# zigduino-v6c.net
KiCad netlist of a schematic drawn in EAGLE
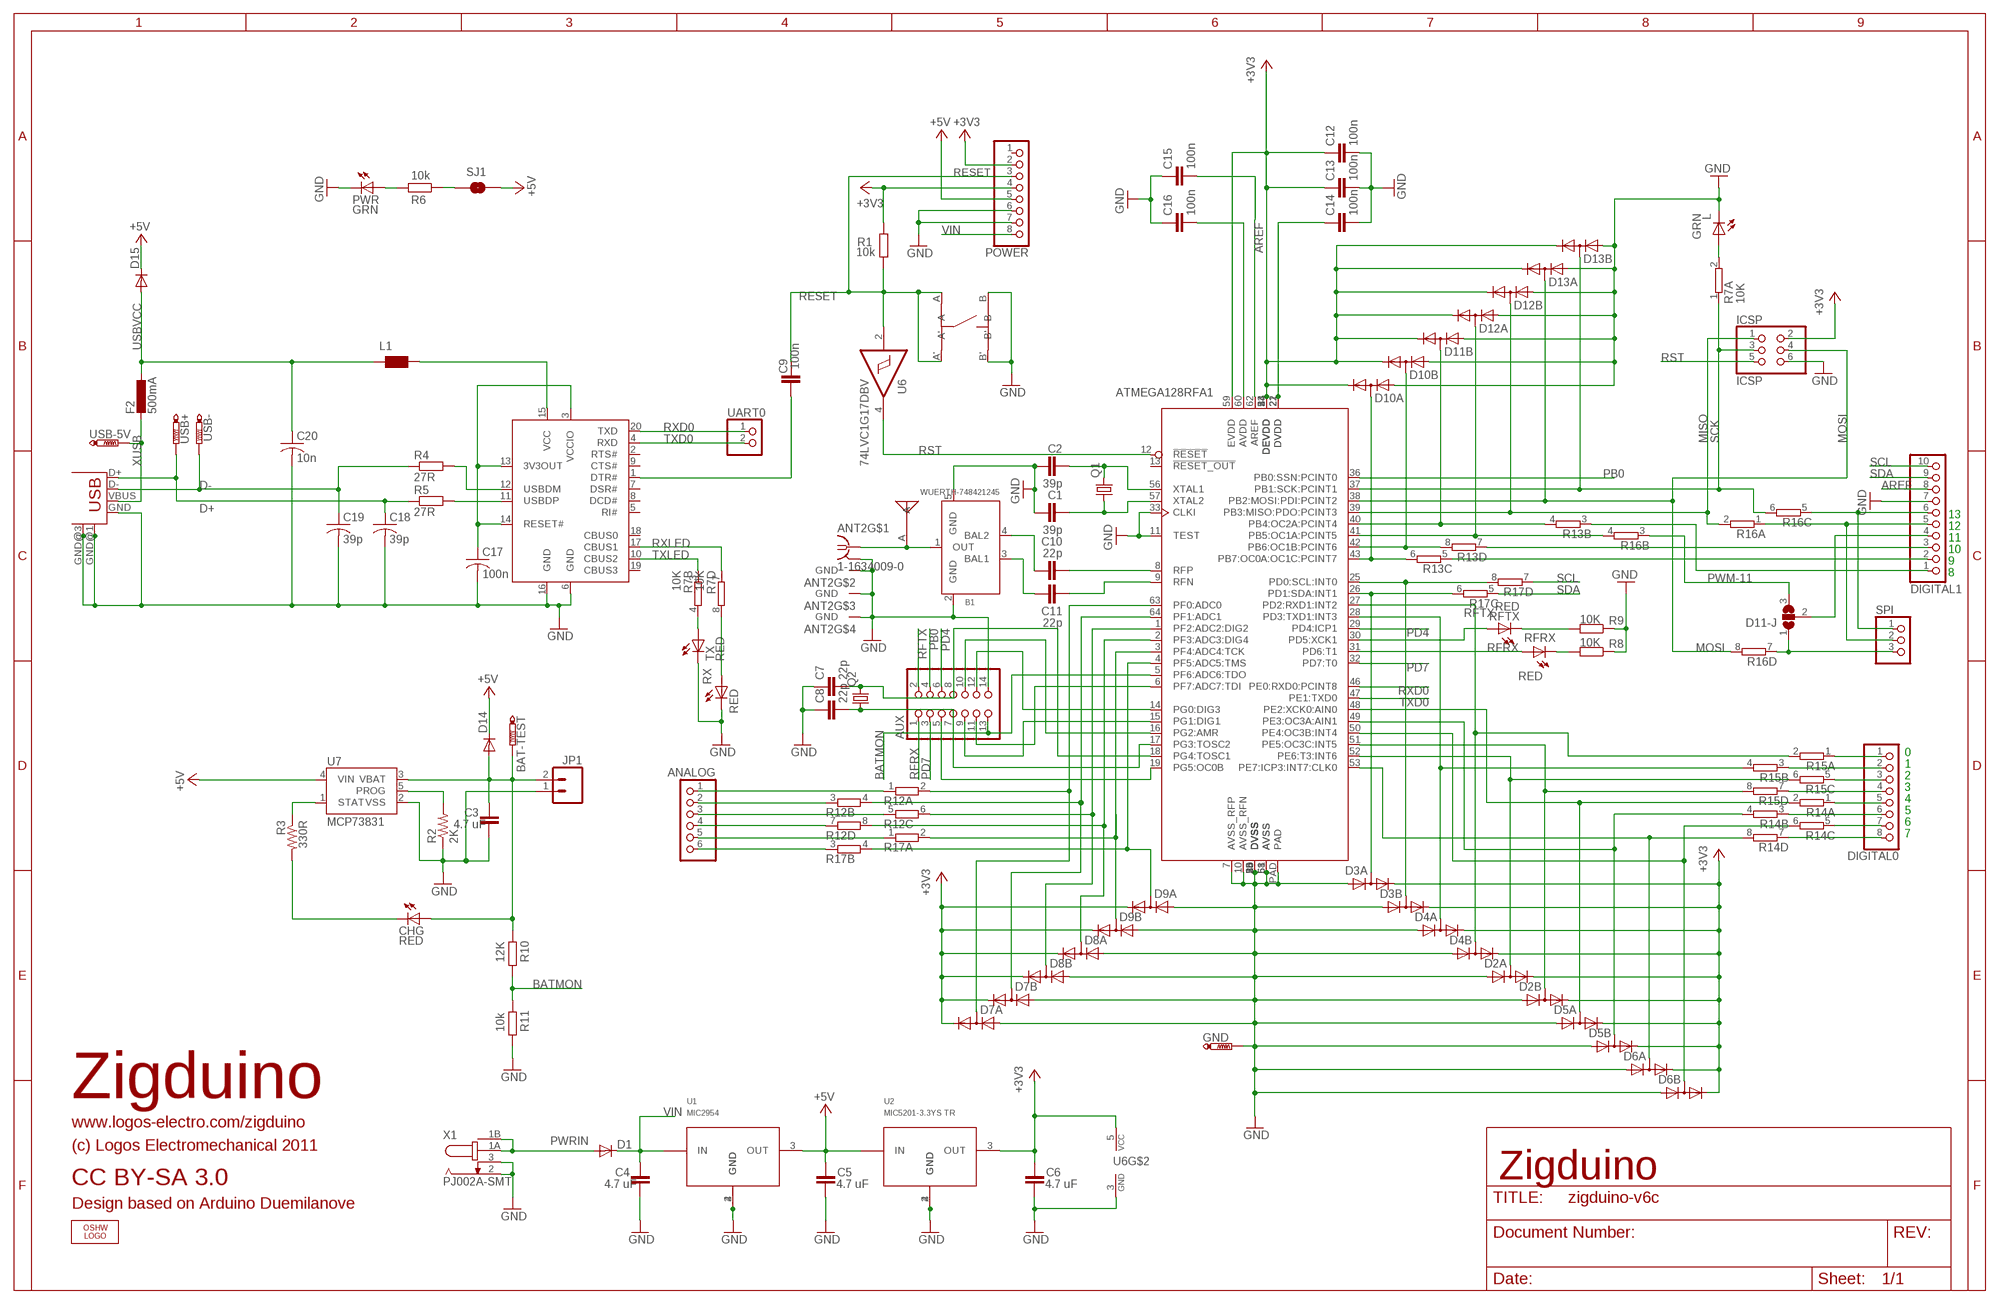
[diagram p0: schematic, sheet 1]

(export (version "E")
  (design (tool "Eeschema 10.0.6"))
  (components
    (comp (ref "ANALOG")
      (value "PINHD-1X6")
      (footprint "eagle-import:1X06")
      (fields (field (name "PARTNO") "19742"))
      (libsource (lib "eagle-import") (part "PINHD-1X6"))
    )
    (comp (ref "ANT1")
      (value "MOLEX-ANT")
      (footprint "eagle-import:MOLEX-ANT")
      (fields (field (name "PARTNO") "0479480001"))
      (libsource (lib "eagle-import") (part "MOLEX-ANT"))
    )
    (comp (ref "ANT2")
      (value "1-1634009-0")
      (footprint "eagle-import:MMCX-THRU")
      (fields (field (name "BOM") "EXCLUDE") (field (name "DNP") "T"))
      (libsource (lib "eagle-import") (part "1-1634009-0"))
    )
    (comp (ref "AUX")
      (value "PINHD-2X7_2.00")
      (footprint "eagle-import:2X07M")
      (fields (field (name "PARTNO") "00217"))
      (libsource (lib "eagle-import") (part "PINHD-2X7_2.00"))
    )
    (comp (ref "B1")
      (value "WUERTH-748421245")
      (footprint "eagle-import:WURTH-BALUN")
      (fields (field (name "PARTNO") "748421245"))
      (libsource (lib "eagle-import") (part "WUERTH-748421245"))
    )
    (comp (ref "BAT-TEST")
      (value "PTR1TP13SQ")
      (footprint "eagle-import:TP13SQ")
      (fields (field (name "PARTNO") "TP13"))
      (libsource (lib "eagle-import") (part "PTR1TP13SQ"))
    )
    (comp (ref "C1")
      (value "39p")
      (footprint "eagle-import:C0603")
      (fields (field (name "PARTNO") "C1608C0G1H390J"))
      (libsource (lib "eagle-import") (part "C-EUC0603"))
    )
    (comp (ref "C2")
      (value "39p")
      (footprint "eagle-import:C0603")
      (fields (field (name "PARTNO") "C1608C0G1H390J"))
      (libsource (lib "eagle-import") (part "C-EUC0603"))
    )
    (comp (ref "C3")
      (value "4.7 uF")
      (footprint "eagle-import:C1206")
      (fields (field (name "PARTNO") "C3216Y5V1H475Z"))
      (libsource (lib "eagle-import") (part "C-EUC1206"))
    )
    (comp (ref "C4")
      (value "4.7 uF")
      (footprint "eagle-import:C1206")
      (fields (field (name "PARTNO") "C3216Y5V1H475Z"))
      (libsource (lib "eagle-import") (part "C-EUC1206"))
    )
    (comp (ref "C5")
      (value "4.7 uF")
      (footprint "eagle-import:C1206")
      (fields (field (name "PARTNO") "C3216Y5V1H475Z"))
      (libsource (lib "eagle-import") (part "C-EUC1206"))
    )
    (comp (ref "C6")
      (value "4.7 uF")
      (footprint "eagle-import:C1206")
      (fields (field (name "PARTNO") "C3216Y5V1H475Z"))
      (libsource (lib "eagle-import") (part "C-EUC1206"))
    )
    (comp (ref "C7")
      (value "22p")
      (footprint "eagle-import:C0603")
      (fields (field (name "PARTNO") "GQM1885C1H220JB01D"))
      (libsource (lib "eagle-import") (part "C-EUC0603"))
    )
    (comp (ref "C8")
      (value "22p")
      (footprint "eagle-import:C0603")
      (fields (field (name "PARTNO") "GQM1885C1H220JB01D"))
      (libsource (lib "eagle-import") (part "C-EUC0603"))
    )
    (comp (ref "C9")
      (value "100n")
      (footprint "eagle-import:C0603")
      (fields (field (name "PARTNO") "CC0603MRY5V9BB104"))
      (libsource (lib "eagle-import") (part "C-EUC0603"))
    )
    (comp (ref "C10")
      (value "22p")
      (footprint "eagle-import:C0603")
      (fields (field (name "PARTNO") "GQM1885C1H220JB01D"))
      (libsource (lib "eagle-import") (part "C-EUC0603"))
    )
    (comp (ref "C11")
      (value "22p")
      (footprint "eagle-import:C0603")
      (fields (field (name "PARTNO") "GQM1885C1H220JB01D"))
      (libsource (lib "eagle-import") (part "C-EUC0603"))
    )
    (comp (ref "C12")
      (value "100n")
      (footprint "eagle-import:C0603")
      (fields (field (name "PARTNO") "CC0603MRY5V9BB104"))
      (libsource (lib "eagle-import") (part "C-EUC0603"))
    )
    (comp (ref "C13")
      (value "100n")
      (footprint "eagle-import:C0603")
      (fields (field (name "PARTNO") "CC0603MRY5V9BB104"))
      (libsource (lib "eagle-import") (part "C-EUC0603"))
    )
    (comp (ref "C14")
      (value "100n")
      (footprint "eagle-import:C0603")
      (fields (field (name "PARTNO") "CC0603MRY5V9BB104"))
      (libsource (lib "eagle-import") (part "C-EUC0603"))
    )
    (comp (ref "C15")
      (value "100n")
      (footprint "eagle-import:C0603")
      (fields (field (name "PARTNO") "CC0603MRY5V9BB104"))
      (libsource (lib "eagle-import") (part "C-EUC0603"))
    )
    (comp (ref "C16")
      (value "100n")
      (footprint "eagle-import:C0603")
      (fields (field (name "PARTNO") "CC0603MRY5V9BB104"))
      (libsource (lib "eagle-import") (part "C-EUC0603"))
    )
    (comp (ref "C17")
      (value "100n")
      (footprint "eagle-import:C0603")
      (fields (field (name "PARTNO") "CC0603MRY5V9BB104"))
      (libsource (lib "eagle-import") (part "C-USC0603"))
    )
    (comp (ref "C18")
      (value "39p")
      (footprint "eagle-import:C0603")
      (fields (field (name "PARTNO") "C1608C0G1H390J"))
      (libsource (lib "eagle-import") (part "C-USC0603"))
    )
    (comp (ref "C19")
      (value "39p")
      (footprint "eagle-import:C0603")
      (fields (field (name "PARTNO") "C1608C0G1H390J"))
      (libsource (lib "eagle-import") (part "C-USC0603"))
    )
    (comp (ref "C20")
      (value "10n")
      (footprint "eagle-import:C0603")
      (fields (field (name "PARTNO") "GRM188R71H103KA01D"))
      (libsource (lib "eagle-import") (part "C-USC0603"))
    )
    (comp (ref "CHG")
      (value "RED")
      (footprint "eagle-import:CHIP-LED0603")
      (fields (field (name "PARTNO") "LTST-C193KRKT-5A"))
      (libsource (lib "eagle-import") (part "LEDCHIP-LED0603"))
    )
    (comp (ref "D1")
      (value "DIODE-SMB")
      (footprint "eagle-import:SMB")
      (fields (field (name "PARTNO") "B150B-13-F"))
      (libsource (lib "eagle-import") (part "DIODE-SMB"))
    )
    (comp (ref "D2")
      (value "SD103ASDM")
      (footprint "eagle-import:SOT26")
      (fields
        (field (name "BOM") "INCLUDE")
        (field (name "PARTNO") "SD103ASDM-7")
        (field (name "VOLT") "40V")
      )
      (libsource (lib "eagle-import") (part "SD103ASDM"))
    )
    (comp (ref "D3")
      (value "SD103ASDM")
      (footprint "eagle-import:SOT26")
      (fields
        (field (name "PARTNO") "SD103ASDM-7")
        (field (name "BOM") "INCLUDE")
        (field (name "VOLT") "40V")
      )
      (libsource (lib "eagle-import") (part "SD103ASDM"))
    )
    (comp (ref "D4")
      (value "SD103ASDM")
      (footprint "eagle-import:SOT26")
      (fields
        (field (name "BOM") "INCLUDE")
        (field (name "PARTNO") "SD103ASDM-7")
        (field (name "VOLT") "40V")
      )
      (libsource (lib "eagle-import") (part "SD103ASDM"))
    )
    (comp (ref "D5")
      (value "SD103ASDM")
      (footprint "eagle-import:SOT26")
      (fields
        (field (name "PARTNO") "SD103ASDM-7")
        (field (name "VOLT") "40V")
        (field (name "BOM") "INCLUDE")
      )
      (libsource (lib "eagle-import") (part "SD103ASDM"))
    )
    (comp (ref "D6")
      (value "SD103ASDM")
      (footprint "eagle-import:SOT26")
      (fields
        (field (name "BOM") "INCLUDE")
        (field (name "PARTNO") "SD103ASDM-7")
        (field (name "VOLT") "40V")
      )
      (libsource (lib "eagle-import") (part "SD103ASDM"))
    )
    (comp (ref "D7")
      (value "SD103ASDM")
      (footprint "eagle-import:SOT26")
      (fields
        (field (name "PARTNO") "SD103ASDM-7")
        (field (name "VOLT") "40V")
        (field (name "BOM") "INCLUDE")
      )
      (libsource (lib "eagle-import") (part "SD103ASDM"))
    )
    (comp (ref "D8")
      (value "SD103ASDM")
      (footprint "eagle-import:SOT26")
      (fields
        (field (name "PARTNO") "SD103ASDM-7")
        (field (name "BOM") "INCLUDE")
        (field (name "VOLT") "40V")
      )
      (libsource (lib "eagle-import") (part "SD103ASDM"))
    )
    (comp (ref "D9")
      (value "SD103ASDM")
      (footprint "eagle-import:SOT26")
      (fields
        (field (name "BOM") "INCLUDE")
        (field (name "PARTNO") "SD103ASDM-7")
        (field (name "VOLT") "40V")
      )
      (libsource (lib "eagle-import") (part "SD103ASDM"))
    )
    (comp (ref "D10")
      (value "SD103ASDM")
      (footprint "eagle-import:SOT26")
      (fields
        (field (name "PARTNO") "SD103ASDM-7")
        (field (name "BOM") "INCLUDE")
        (field (name "VOLT") "40V")
      )
      (libsource (lib "eagle-import") (part "SD103ASDM"))
    )
    (comp (ref "D11")
      (value "SD103ASDM")
      (footprint "eagle-import:SOT26")
      (fields (field (name "PARTNO") "SD103ASDM-7"))
      (libsource (lib "eagle-import") (part "SD103ASDM"))
    )
    (comp (ref "D11-J")
      (value "SJ2W")
      (footprint "eagle-import:SJ_2")
      (fields (field (name "PARTNO") "SJ3"))
      (libsource (lib "eagle-import") (part "SJ2W"))
    )
    (comp (ref "D12")
      (value "SD103ASDM")
      (footprint "eagle-import:SOT26")
      (fields
        (field (name "BOM") "INCLUDE")
        (field (name "PARTNO") "SD103ASDM-7")
        (field (name "VOLT") "40V")
      )
      (libsource (lib "eagle-import") (part "SD103ASDM"))
    )
    (comp (ref "D13")
      (value "SD103ASDM")
      (footprint "eagle-import:SOT26")
      (fields
        (field (name "BOM") "INCLUDE")
        (field (name "PARTNO") "SD103ASDM-7")
        (field (name "VOLT") "40V")
      )
      (libsource (lib "eagle-import") (part "SD103ASDM"))
    )
    (comp (ref "D14")
      (value "DIODE-SMB")
      (footprint "eagle-import:SMB")
      (fields (field (name "PARTNO") "B150B-13-F"))
      (libsource (lib "eagle-import") (part "DIODE-SMB"))
    )
    (comp (ref "D15")
      (value "DIODE-SMB")
      (footprint "eagle-import:SMB")
      (fields (field (name "PARTNO") "B150B-13-F"))
      (libsource (lib "eagle-import") (part "DIODE-SMB"))
    )
    (comp (ref "DIGITAL0")
      (value "PINHD-1X8")
      (footprint "eagle-import:1X08")
      (fields (field (name "PARTNO") "19743"))
      (libsource (lib "eagle-import") (part "PINHD-1X8"))
    )
    (comp (ref "DIGITAL1")
      (value "PINHD-1X10")
      (footprint "eagle-import:1X10")
      (fields (field (name "PARTNO") "20083"))
      (libsource (lib "eagle-import") (part "PINHD-1X10"))
    )
    (comp (ref "F2")
      (value "500mA")
      (footprint "eagle-import:L1812")
      (fields (field (name "PARTNO") "MF-MSMF050-2"))
      (libsource (lib "eagle-import") (part "L-EUL1812"))
    )
    (comp (ref "GND")
      (value "PTR1TP13SQ")
      (footprint "eagle-import:TP13SQ")
      (fields (field (name "PARTNO") "TP13"))
      (libsource (lib "eagle-import") (part "PTR1TP13SQ"))
    )
    (comp (ref "ICSP")
      (value "ICSP")
      (footprint "eagle-import:2X03")
      (fields (field (name "PARTNO") "961206-6404-AR"))
      (libsource (lib "eagle-import") (part "PINHD-2X3"))
    )
    (comp (ref "JP1")
      (value "M02-JST-2MM-SMT")
      (footprint "eagle-import:S2B-PH")
      (fields (field (name "PARTNO") "S2B-PH-SM4-TB(LF)(SN)"))
      (libsource (lib "eagle-import") (part "M02-JST-2MM-SMT"))
    )
    (comp (ref "L")
      (value "GRN")
      (footprint "eagle-import:CHIP-LED0603")
      (fields (field (name "PARTNO") "LTST-C193KGKT-5A"))
      (libsource (lib "eagle-import") (part "LEDCHIP-LED0603"))
    )
    (comp (ref "L1")
      (value "WE-CBF_0805")
      (footprint "eagle-import:0805")
      (fields (field (name "PARTNO") "MI0805K400R-10"))
      (libsource (lib "eagle-import") (part "WE-CBF_0805"))
    )
    (comp (ref "LOGO1")
      (value "OSHW_LOGO_FILLX0200-NT")
      (footprint "eagle-import:OSHW_FILLX200_NOTEXT")
      (libsource (lib "eagle-import") (part "OSHW_LOGO_FILLX0200-NT"))
    )
    (comp (ref "POWER")
      (value "PINHD-1X8")
      (footprint "eagle-import:1X08")
      (fields (field (name "PARTNO") "19743"))
      (libsource (lib "eagle-import") (part "PINHD-1X8"))
    )
    (comp (ref "PWR")
      (value "GRN")
      (footprint "eagle-import:CHIP-LED0603")
      (fields (field (name "PARTNO") "LTST-C193KGKT-5A"))
      (libsource (lib "eagle-import") (part "LEDCHIP-LED0603"))
    )
    (comp (ref "Q1")
      (value "CRYSTALCSM-3X")
      (footprint "eagle-import:CSM-3X")
      (fields (field (name "PARTNO") "ECS-160-20-3X-TR"))
      (libsource (lib "eagle-import") (part "CRYSTALCSM-3X"))
    )
    (comp (ref "Q2")
      (value "CRYSTALTC26H")
      (footprint "eagle-import:TC26H")
      (libsource (lib "eagle-import") (part "CRYSTALTC26H"))
    )
    (comp (ref "R1")
      (value "10k")
      (footprint "eagle-import:R0603")
      (fields (field (name "PARTNO") "RMCF0603FT10K0"))
      (libsource (lib "eagle-import") (part "R-EU_R0603"))
    )
    (comp (ref "R2")
      (value "2K")
      (footprint "eagle-import:R0603")
      (fields (field (name "PARTNO") "RC0603FR-072KL"))
      (libsource (lib "eagle-import") (part "R-US_R0603"))
    )
    (comp (ref "R3")
      (value "330R")
      (footprint "eagle-import:R0603")
      (fields (field (name "PARTNO") "RC0603FR-07330RL"))
      (libsource (lib "eagle-import") (part "R-US_R0603"))
    )
    (comp (ref "R4")
      (value "27R")
      (footprint "eagle-import:R0603")
      (fields (field (name "PARTNO") "RC0603JR-0727RL"))
      (libsource (lib "eagle-import") (part "R-EU_R0603"))
    )
    (comp (ref "R5")
      (value "27R")
      (footprint "eagle-import:R0603")
      (fields (field (name "PARTNO") "RC0603JR-0727RL"))
      (libsource (lib "eagle-import") (part "R-EU_R0603"))
    )
    (comp (ref "R6")
      (value "10k")
      (footprint "eagle-import:R0603")
      (fields (field (name "PARTNO") "RMCF0603FT10K0"))
      (libsource (lib "eagle-import") (part "R-EU_R0603"))
    )
    (comp (ref "R7")
      (value "10K")
      (footprint "eagle-import:CTS742C083-RES")
      (fields (field (name "BOM") "INCLUDE") (field (name "PARTNO") "742C083103JPTR"))
      (libsource (lib "eagle-import") (part "4R-NCTS742C083"))
    )
    (comp (ref "R8")
      (value "10K")
      (footprint "eagle-import:R0603")
      (fields (field (name "PARTNO") "RMCF0603FT10K0"))
      (libsource (lib "eagle-import") (part "R-EU_R0603"))
    )
    (comp (ref "R9")
      (value "10K")
      (footprint "eagle-import:R0603")
      (fields (field (name "PARTNO") "RMCF0603FT10K0"))
      (libsource (lib "eagle-import") (part "R-EU_R0603"))
    )
    (comp (ref "R10")
      (value "12K")
      (footprint "eagle-import:R0603")
      (fields (field (name "PARTNO") "RMCF0603FT12K0"))
      (libsource (lib "eagle-import") (part "R-EU_R0603"))
    )
    (comp (ref "R11")
      (value "10k")
      (footprint "eagle-import:R0603")
      (fields (field (name "PARTNO") "RMCF0603FT10K0"))
      (libsource (lib "eagle-import") (part "R-EU_R0603"))
    )
    (comp (ref "R12")
      (value "4R-NCTS742C083")
      (footprint "eagle-import:CTS742C083-RES")
      (fields (field (name "PARTNO") "742C083101JPTR") (field (name "BOM") "INCLUDE"))
      (libsource (lib "eagle-import") (part "4R-NCTS742C083"))
    )
    (comp (ref "R13")
      (value "4R-NCTS742C083")
      (footprint "eagle-import:CTS742C083-RES")
      (fields (field (name "PARTNO") "742C083101JPTR") (field (name "BOM") "INCLUDE"))
      (libsource (lib "eagle-import") (part "4R-NCTS742C083"))
    )
    (comp (ref "R14")
      (value "4R-NCTS742C083")
      (footprint "eagle-import:CTS742C083-RES")
      (fields (field (name "BOM") "INCLUDE") (field (name "PARTNO") "742C083101JPTR"))
      (libsource (lib "eagle-import") (part "4R-NCTS742C083"))
    )
    (comp (ref "R15")
      (value "4R-NCTS742C083")
      (footprint "eagle-import:CTS742C083-RES")
      (fields (field (name "BOM") "INCLUDE") (field (name "PARTNO") "742C083101JPTR"))
      (libsource (lib "eagle-import") (part "4R-NCTS742C083"))
    )
    (comp (ref "R16")
      (value "4R-NCTS742C083")
      (footprint "eagle-import:CTS742C083-RES")
      (fields (field (name "BOM") "INCLUDE") (field (name "PARTNO") "742C083101JPTR"))
      (libsource (lib "eagle-import") (part "4R-NCTS742C083"))
    )
    (comp (ref "R17")
      (value "4R-NCTS742C083")
      (footprint "eagle-import:CTS742C083-RES")
      (fields (field (name "BOM") "INCLUDE") (field (name "PARTNO") "742C083101JPTR"))
      (libsource (lib "eagle-import") (part "4R-NCTS742C083"))
    )
    (comp (ref "RFRX")
      (value "RED")
      (footprint "eagle-import:CHIP-LED0603")
      (fields (field (name "PARTNO") "LTST-C193KRKT-5A"))
      (libsource (lib "eagle-import") (part "LEDCHIP-LED0603"))
    )
    (comp (ref "RFTX")
      (value "RED")
      (footprint "eagle-import:CHIP-LED0603")
      (fields (field (name "PARTNO") "LTST-C193KRKT-5A"))
      (libsource (lib "eagle-import") (part "LEDCHIP-LED0603"))
    )
    (comp (ref "RX")
      (value "RED")
      (footprint "eagle-import:CHIP-LED0603")
      (fields (field (name "PARTNO") "LTST-C193KRKT-5A"))
      (libsource (lib "eagle-import") (part "LEDCHIP-LED0603"))
    )
    (comp (ref "SJ1")
      (value "SOLDERJUMPERTRACE")
      (footprint "eagle-import:SJ_2S-TRACE")
      (libsource (lib "eagle-import") (part "SOLDERJUMPERTRACE"))
    )
    (comp (ref "SPI")
      (value "PINHD-1X3")
      (footprint "eagle-import:1X03")
      (fields (field (name "PARTNO") "20152"))
      (libsource (lib "eagle-import") (part "PINHD-1X3"))
    )
    (comp (ref "SW1")
      (value "EVQ-PSD02K")
      (footprint "eagle-import:EVQPSD02K")
      (libsource (lib "eagle-import") (part "EVQ-PSD02K"))
    )
    (comp (ref "TX")
      (value "RED")
      (footprint "eagle-import:CHIP-LED0603")
      (fields (field (name "PARTNO") "LTST-C193KRKT-5A"))
      (libsource (lib "eagle-import") (part "LEDCHIP-LED0603"))
    )
    (comp (ref "U1")
      (value "MIC2954")
      (footprint "eagle-import:SOT223")
      (fields (field (name "PARTNO") "MIC2954-03WS-TR"))
      (libsource (lib "eagle-import") (part "MIC2954"))
    )
    (comp (ref "U2")
      (value "MIC5201-3.3YS TR")
      (footprint "eagle-import:SOT223")
      (libsource (lib "eagle-import") (part "MIC5201-3.3BS"))
    )
    (comp (ref "U3")
      (value "ATMEGA128RFA1")
      (footprint "eagle-import:QFN64")
      (fields (field (name "PARTNO") "ATMEGA128RFA1-ZUR"))
      (libsource (lib "eagle-import") (part "ATMEGA128RFA1"))
    )
    (comp (ref "U4")
      (value "FT231XS-R")
      (footprint "eagle-import:SSOP20")
      (libsource (lib "eagle-import") (part "FT231XS-R"))
    )
    (comp (ref "U6")
      (value "74LVC1G17DBV")
      (footprint "eagle-import:SOT23-5")
      (fields (field (name "BOM") "INCLUDE") (field (name "PARTNO") "SN74LVC1G17DBVR"))
      (libsource (lib "eagle-import") (part "741G17DBVLVC"))
    )
    (comp (ref "U7")
      (value "MCP73831")
      (footprint "eagle-import:SOT23-5")
      (fields (field (name "PARTNO") "MCP73831T-2ACI/OT"))
      (libsource (lib "eagle-import") (part "MCP73831"))
    )
    (comp (ref "UART0")
      (value "PINHD-1X2")
      (footprint "eagle-import:1X02")
      (fields (field (name "PARTNO") "00522"))
      (libsource (lib "eagle-import") (part "PINHD-1X2"))
    )
    (comp (ref "USB")
      (value "USB-MB-S")
      (footprint "eagle-import:USB-MB-S")
      (fields (field (name "PARTNO") "20236"))
      (libsource (lib "eagle-import") (part "USB-MB-S"))
    )
    (comp (ref "USB+")
      (value "PTR1TP13SQ")
      (footprint "eagle-import:TP13SQ")
      (fields (field (name "PARTNO") "TP13"))
      (libsource (lib "eagle-import") (part "PTR1TP13SQ"))
    )
    (comp (ref "USB-")
      (value "PTR1TP13SQ")
      (footprint "eagle-import:TP13SQ")
      (fields (field (name "PARTNO") "TP13"))
      (libsource (lib "eagle-import") (part "PTR1TP13SQ"))
    )
    (comp (ref "USB-5V")
      (value "PTR1TP13SQ")
      (footprint "eagle-import:TP13SQ")
      (fields (field (name "PARTNO") "TP13"))
      (libsource (lib "eagle-import") (part "PTR1TP13SQ"))
    )
    (comp (ref "X1")
      (value "PJ002A-SMT")
      (footprint "eagle-import:PJ002A-SMT")
      (fields (field (name "PARTNO") "PJ-002AH-SMT"))
      (libsource (lib "eagle-import") (part "PJ002A-SMT"))
    )
  )
  (nets
    (net (code "1") (name "+3V3") (class "Default")
      (node (ref "C12") (pin "1") (pinfunction "1_1") (pintype "passive"))
      (node (ref "C13") (pin "1") (pinfunction "1_1") (pintype "passive"))
      (node (ref "C6") (pin "1") (pinfunction "1_1") (pintype "passive"))
      (node (ref "D10") (pin "2") (pinfunction "C_2") (pintype "passive"))
      (node (ref "D10") (pin "5") (pinfunction "C_5") (pintype "passive"))
      (node (ref "D11") (pin "5") (pinfunction "C_5") (pintype "passive"))
      (node (ref "D12") (pin "2") (pinfunction "C_2") (pintype "passive"))
      (node (ref "D12") (pin "5") (pinfunction "C_5") (pintype "passive"))
      (node (ref "D13") (pin "2") (pinfunction "C_2") (pintype "passive"))
      (node (ref "D13") (pin "5") (pinfunction "C_5") (pintype "passive"))
      (node (ref "D2") (pin "2") (pinfunction "C_2") (pintype "passive"))
      (node (ref "D2") (pin "5") (pinfunction "C_5") (pintype "passive"))
      (node (ref "D3") (pin "2") (pinfunction "C_2") (pintype "passive"))
      (node (ref "D3") (pin "5") (pinfunction "C_5") (pintype "passive"))
      (node (ref "D4") (pin "2") (pinfunction "C_2") (pintype "passive"))
      (node (ref "D4") (pin "5") (pinfunction "C_5") (pintype "passive"))
      (node (ref "D5") (pin "2") (pinfunction "C_2") (pintype "passive"))
      (node (ref "D5") (pin "5") (pinfunction "C_5") (pintype "passive"))
      (node (ref "D6") (pin "2") (pinfunction "C_2") (pintype "passive"))
      (node (ref "D6") (pin "5") (pinfunction "C_5") (pintype "passive"))
      (node (ref "D7") (pin "2") (pinfunction "C_2") (pintype "passive"))
      (node (ref "D7") (pin "5") (pinfunction "C_5") (pintype "passive"))
      (node (ref "D8") (pin "2") (pinfunction "C_2") (pintype "passive"))
      (node (ref "D8") (pin "5") (pinfunction "C_5") (pintype "passive"))
      (node (ref "D9") (pin "2") (pinfunction "C_2") (pintype "passive"))
      (node (ref "D9") (pin "5") (pinfunction "C_5") (pintype "passive"))
      (node (ref "ICSP") (pin "2") (pinfunction "2_2") (pintype "passive"))
      (node (ref "POWER") (pin "2") (pinfunction "2_2") (pintype "passive"))
      (node (ref "POWER") (pin "4") (pinfunction "4_4") (pintype "passive"))
      (node (ref "R1") (pin "2") (pinfunction "2_2") (pintype "passive"))
      (node (ref "U2") (pin "3") (pinfunction "OUT_3") (pintype "bidirectional"))
      (node (ref "U3") (pin "23") (pinfunction "DEVDD_23") (pintype "bidirectional"))
      (node (ref "U3") (pin "34") (pinfunction "DEVDD_34") (pintype "bidirectional"))
      (node (ref "U3") (pin "44") (pinfunction "DEVDD_44") (pintype "bidirectional"))
      (node (ref "U3") (pin "54") (pinfunction "DEVDD_54") (pintype "bidirectional"))
      (node (ref "U3") (pin "59") (pinfunction "EVDD_59") (pintype "bidirectional"))
      (node (ref "U6") (pin "5") (pinfunction "VCC_5") (pintype "power_in"))
    )
    (net (code "2") (name "+5V") (class "Default")
      (node (ref "C5") (pin "1") (pinfunction "1_1") (pintype "passive"))
      (node (ref "D14") (pin "C") (pinfunction "C_C") (pintype "passive"))
      (node (ref "D15") (pin "C") (pinfunction "C_C") (pintype "passive"))
      (node (ref "POWER") (pin "5") (pinfunction "5_5") (pintype "passive"))
      (node (ref "SJ1") (pin "2") (pinfunction "2_2") (pintype "passive"))
      (node (ref "U1") (pin "3") (pinfunction "OUT_3") (pintype "bidirectional"))
      (node (ref "U2") (pin "1") (pinfunction "IN_1") (pintype "bidirectional"))
      (node (ref "U7") (pin "4") (pinfunction "VIN_4") (pintype "power_in"))
    )
    (net (code "3") (name "/AREF") (class "Default")
      (node (ref "C15") (pin "2") (pinfunction "2_2") (pintype "passive"))
      (node (ref "DIGITAL1") (pin "8") (pinfunction "8_8") (pintype "passive"))
      (node (ref "U3") (pin "62") (pinfunction "AREF_62") (pintype "bidirectional"))
    )
    (net (code "4") (name "/BATMON") (class "Default")
      (node (ref "AUX") (pin "13") (pinfunction "13_13") (pintype "passive"))
      (node (ref "R10") (pin "2") (pinfunction "2_2") (pintype "passive"))
      (node (ref "R11") (pin "1") (pinfunction "1_1") (pintype "passive"))
      (node (ref "U3") (pin "5") (pinfunction "PF6:ADC6:TDO_5") (pintype "bidirectional"))
    )
    (net (code "5") (name "/D+") (class "Default")
      (node (ref "C18") (pin "1") (pinfunction "1_1") (pintype "passive"))
      (node (ref "R5") (pin "1") (pinfunction "1_1") (pintype "passive"))
      (node (ref "USB") (pin "D+") (pinfunction "D+_D+") (pintype "bidirectional"))
      (node (ref "USB+") (pin "TP") (pinfunction "TP_TP") (pintype "input"))
    )
    (net (code "6") (name "/D-") (class "Default")
      (node (ref "C19") (pin "1") (pinfunction "1_1") (pintype "passive"))
      (node (ref "R4") (pin "1") (pinfunction "1_1") (pintype "passive"))
      (node (ref "USB") (pin "D-") (pinfunction "D-_D-") (pintype "bidirectional"))
      (node (ref "USB-") (pin "TP") (pinfunction "TP_TP") (pintype "input"))
    )
    (net (code "7") (name "/MISO") (class "Default")
      (node (ref "D12") (pin "1") (pinfunction "AC_1") (pintype "passive"))
      (node (ref "ICSP") (pin "1") (pinfunction "1_1") (pintype "passive"))
      (node (ref "R16") (pin "2") (pinfunction "2_2") (pintype "passive"))
      (node (ref "U3") (pin "39") (pinfunction "PB3:MISO:PDO:PCINT3_39") (pintype "bidirectional"))
    )
    (net (code "8") (name "/MOSI") (class "Default")
      (node (ref "D13") (pin "4") (pinfunction "AC_4") (pintype "passive"))
      (node (ref "ICSP") (pin "4") (pinfunction "4_4") (pintype "passive"))
      (node (ref "R16") (pin "8") (pinfunction "2_8") (pintype "passive"))
      (node (ref "U3") (pin "38") (pinfunction "PB2:MOSI:PDI:PCINT2_38") (pintype "bidirectional"))
    )
    (net (code "9") (name "/PB0") (class "Default")
      (node (ref "AUX") (pin "4") (pinfunction "4_4") (pintype "passive"))
      (node (ref "U3") (pin "36") (pinfunction "PB0:SSN:PCINT0_36") (pintype "bidirectional"))
    )
    (net (code "10") (name "/PD4") (class "Default")
      (node (ref "AUX") (pin "6") (pinfunction "6_6") (pintype "passive"))
      (node (ref "U3") (pin "29") (pinfunction "PD4:ICP1_29") (pintype "bidirectional"))
    )
    (net (code "11") (name "/PD7") (class "Default")
      (node (ref "AUX") (pin "3") (pinfunction "3_3") (pintype "passive"))
      (node (ref "U3") (pin "32") (pinfunction "PD7:T0_32") (pintype "bidirectional"))
    )
    (net (code "12") (name "/PWM-11") (class "Default")
      (node (ref "D11-J") (pin "3") (pinfunction "3_3") (pintype "passive"))
      (node (ref "R16") (pin "3") (pinfunction "1_3") (pintype "passive"))
    )
    (net (code "13") (name "/PWRIN") (class "Default")
      (node (ref "D1") (pin "A") (pinfunction "A_A") (pintype "passive"))
      (node (ref "X1") (pin "1A") (pinfunction "1A_1A") (pintype "passive"))
      (node (ref "X1") (pin "1B") (pinfunction "1B_1B") (pintype "passive"))
    )
    (net (code "14") (name "/RESET") (class "Default")
      (node (ref "C9") (pin "2") (pinfunction "2_2") (pintype "passive"))
      (node (ref "POWER") (pin "3") (pinfunction "3_3") (pintype "passive"))
      (node (ref "R1") (pin "1") (pinfunction "1_1") (pintype "passive"))
      (node (ref "SW1") (pin "A") (pinfunction "A_A") (pintype "bidirectional"))
      (node (ref "SW1") (pin "A'") (pinfunction "A'_A'") (pintype "bidirectional"))
      (node (ref "U6") (pin "2") (pinfunction "I_2") (pintype "input"))
    )
    (net (code "15") (name "/RFRX") (class "Default")
      (node (ref "AUX") (pin "1") (pinfunction "1_1") (pintype "passive"))
      (node (ref "RFRX") (pin "A") (pinfunction "A_A") (pintype "passive"))
      (node (ref "U3") (pin "31") (pinfunction "PD6:T1_31") (pintype "bidirectional"))
    )
    (net (code "16") (name "/RFTX") (class "Default")
      (node (ref "AUX") (pin "2") (pinfunction "2_2") (pintype "passive"))
      (node (ref "RFTX") (pin "A") (pinfunction "A_A") (pintype "passive"))
      (node (ref "U3") (pin "30") (pinfunction "PD5:XCK1_30") (pintype "bidirectional"))
    )
    (net (code "17") (name "/RST") (class "Default")
      (node (ref "ICSP") (pin "5") (pinfunction "5_5") (pintype "passive"))
      (node (ref "U3") (pin "12") (pinfunction "~{RESET}_12") (pintype "bidirectional"))
      (node (ref "U6") (pin "4") (pinfunction "O_4") (pintype "output"))
    )
    (net (code "18") (name "/RXD0") (class "Default")
      (node (ref "U3") (pin "46") (pinfunction "PE0:RXD0:PCINT8_46") (pintype "bidirectional"))
      (node (ref "U4") (pin "20") (pinfunction "TXD_20") (pintype "bidirectional"))
      (node (ref "UART0") (pin "1") (pinfunction "1_1") (pintype "passive"))
    )
    (net (code "19") (name "/RXLED") (class "Default")
      (node (ref "R7") (pin "7") (pinfunction "1_7") (pintype "passive"))
      (node (ref "U4") (pin "17") (pinfunction "CBUS1_17") (pintype "bidirectional"))
    )
    (net (code "20") (name "/SCK") (class "Default")
      (node (ref "D13") (pin "1") (pinfunction "AC_1") (pintype "passive"))
      (node (ref "ICSP") (pin "3") (pinfunction "3_3") (pintype "passive"))
      (node (ref "R16") (pin "6") (pinfunction "2_6") (pintype "passive"))
      (node (ref "R7") (pin "1") (pinfunction "1_1") (pintype "passive"))
      (node (ref "U3") (pin "37") (pinfunction "PB1:SCK:PCINT1_37") (pintype "bidirectional"))
    )
    (net (code "21") (name "/SCL") (class "Default")
      (node (ref "DIGITAL1") (pin "10") (pinfunction "10_10") (pintype "passive"))
      (node (ref "R17") (pin "7") (pinfunction "1_7") (pintype "passive"))
    )
    (net (code "22") (name "/SDA") (class "Default")
      (node (ref "DIGITAL1") (pin "9") (pinfunction "9_9") (pintype "passive"))
      (node (ref "R17") (pin "5") (pinfunction "1_5") (pintype "passive"))
    )
    (net (code "23") (name "/TXD0") (class "Default")
      (node (ref "U3") (pin "47") (pinfunction "PE1:TXD0_47") (pintype "bidirectional"))
      (node (ref "U4") (pin "4") (pinfunction "RXD_4") (pintype "bidirectional"))
      (node (ref "UART0") (pin "2") (pinfunction "2_2") (pintype "passive"))
    )
    (net (code "24") (name "/TXLED") (class "Default")
      (node (ref "R7") (pin "3") (pinfunction "1_3") (pintype "passive"))
      (node (ref "U4") (pin "10") (pinfunction "CBUS2_10") (pintype "bidirectional"))
    )
    (net (code "25") (name "/USBVCC") (class "Default")
      (node (ref "C20") (pin "1") (pinfunction "1_1") (pintype "passive"))
      (node (ref "D15") (pin "A") (pinfunction "A_A") (pintype "passive"))
      (node (ref "F2") (pin "1") (pinfunction "1_1") (pintype "passive"))
      (node (ref "L1") (pin "1") (pinfunction "1_1") (pintype "passive"))
    )
    (net (code "26") (name "/VIN") (class "Default")
      (node (ref "C4") (pin "1") (pinfunction "1_1") (pintype "passive"))
      (node (ref "D1") (pin "C") (pinfunction "C_C") (pintype "passive"))
      (node (ref "POWER") (pin "8") (pinfunction "8_8") (pintype "passive"))
      (node (ref "U1") (pin "1") (pinfunction "IN_1") (pintype "bidirectional"))
    )
    (net (code "27") (name "/XUSB") (class "Default")
      (node (ref "F2") (pin "2") (pinfunction "2_2") (pintype "passive"))
      (node (ref "USB") (pin "VBUS") (pinfunction "VBUS_VBUS") (pintype "bidirectional"))
      (node (ref "USB-5V") (pin "TP") (pinfunction "TP_TP") (pintype "input"))
    )
    (net (code "28") (name "GND") (class "Default")
      (node (ref "ANT2") (pin "G@0") (pinfunction "GND_G@0") (pintype "power_in"))
      (node (ref "ANT2") (pin "G@1") (pinfunction "GND_G@1") (pintype "power_in"))
      (node (ref "ANT2") (pin "G@2") (pinfunction "GND_G@2") (pintype "power_in"))
      (node (ref "ANT2") (pin "G@3") (pinfunction "GND_G@3") (pintype "power_in"))
      (node (ref "AUX") (pin "14") (pinfunction "14_14") (pintype "passive"))
      (node (ref "B1") (pin "2") (pinfunction "GND_2") (pintype "bidirectional"))
      (node (ref "B1") (pin "5") (pinfunction "GND_5") (pintype "bidirectional"))
      (node (ref "C1") (pin "1") (pinfunction "1_1") (pintype "passive"))
      (node (ref "C12") (pin "2") (pinfunction "2_2") (pintype "passive"))
      (node (ref "C13") (pin "2") (pinfunction "2_2") (pintype "passive"))
      (node (ref "C14") (pin "2") (pinfunction "2_2") (pintype "passive"))
      (node (ref "C15") (pin "1") (pinfunction "1_1") (pintype "passive"))
      (node (ref "C16") (pin "1") (pinfunction "1_1") (pintype "passive"))
      (node (ref "C17") (pin "2") (pinfunction "2_2") (pintype "passive"))
      (node (ref "C18") (pin "2") (pinfunction "2_2") (pintype "passive"))
      (node (ref "C19") (pin "2") (pinfunction "2_2") (pintype "passive"))
      (node (ref "C2") (pin "1") (pinfunction "1_1") (pintype "passive"))
      (node (ref "C20") (pin "2") (pinfunction "2_2") (pintype "passive"))
      (node (ref "C3") (pin "2") (pinfunction "2_2") (pintype "passive"))
      (node (ref "C4") (pin "2") (pinfunction "2_2") (pintype "passive"))
      (node (ref "C5") (pin "2") (pinfunction "2_2") (pintype "passive"))
      (node (ref "C6") (pin "2") (pinfunction "2_2") (pintype "passive"))
      (node (ref "C7") (pin "1") (pinfunction "1_1") (pintype "passive"))
      (node (ref "C8") (pin "1") (pinfunction "1_1") (pintype "passive"))
      (node (ref "D10") (pin "3") (pinfunction "A_3") (pintype "passive"))
      (node (ref "D10") (pin "6") (pinfunction "A_6") (pintype "passive"))
      (node (ref "D11") (pin "6") (pinfunction "A_6") (pintype "passive"))
      (node (ref "D12") (pin "3") (pinfunction "A_3") (pintype "passive"))
      (node (ref "D12") (pin "6") (pinfunction "A_6") (pintype "passive"))
      (node (ref "D13") (pin "3") (pinfunction "A_3") (pintype "passive"))
      (node (ref "D13") (pin "6") (pinfunction "A_6") (pintype "passive"))
      (node (ref "D2") (pin "3") (pinfunction "A_3") (pintype "passive"))
      (node (ref "D2") (pin "6") (pinfunction "A_6") (pintype "passive"))
      (node (ref "D3") (pin "3") (pinfunction "A_3") (pintype "passive"))
      (node (ref "D3") (pin "6") (pinfunction "A_6") (pintype "passive"))
      (node (ref "D4") (pin "3") (pinfunction "A_3") (pintype "passive"))
      (node (ref "D4") (pin "6") (pinfunction "A_6") (pintype "passive"))
      (node (ref "D5") (pin "3") (pinfunction "A_3") (pintype "passive"))
      (node (ref "D5") (pin "6") (pinfunction "A_6") (pintype "passive"))
      (node (ref "D6") (pin "3") (pinfunction "A_3") (pintype "passive"))
      (node (ref "D6") (pin "6") (pinfunction "A_6") (pintype "passive"))
      (node (ref "D7") (pin "3") (pinfunction "A_3") (pintype "passive"))
      (node (ref "D7") (pin "6") (pinfunction "A_6") (pintype "passive"))
      (node (ref "D8") (pin "3") (pinfunction "A_3") (pintype "passive"))
      (node (ref "D8") (pin "6") (pinfunction "A_6") (pintype "passive"))
      (node (ref "D9") (pin "3") (pinfunction "A_3") (pintype "passive"))
      (node (ref "D9") (pin "6") (pinfunction "A_6") (pintype "passive"))
      (node (ref "DIGITAL1") (pin "7") (pinfunction "7_7") (pintype "passive"))
      (node (ref "GND") (pin "TP") (pinfunction "TP_TP") (pintype "input"))
      (node (ref "ICSP") (pin "6") (pinfunction "6_6") (pintype "passive"))
      (node (ref "JP1") (pin "1") (pinfunction "1_1") (pintype "passive"))
      (node (ref "L") (pin "C") (pinfunction "C_C") (pintype "passive"))
      (node (ref "POWER") (pin "6") (pinfunction "6_6") (pintype "passive"))
      (node (ref "POWER") (pin "7") (pinfunction "7_7") (pintype "passive"))
      (node (ref "PWR") (pin "C") (pinfunction "C_C") (pintype "passive"))
      (node (ref "R11") (pin "2") (pinfunction "2_2") (pintype "passive"))
      (node (ref "R2") (pin "1") (pinfunction "1_1") (pintype "passive"))
      (node (ref "R8") (pin "1") (pinfunction "1_1") (pintype "passive"))
      (node (ref "R9") (pin "1") (pinfunction "1_1") (pintype "passive"))
      (node (ref "RX") (pin "C") (pinfunction "C_C") (pintype "passive"))
      (node (ref "SW1") (pin "B") (pinfunction "B_B") (pintype "bidirectional"))
      (node (ref "SW1") (pin "B'") (pinfunction "B'_B'") (pintype "bidirectional"))
      (node (ref "TX") (pin "C") (pinfunction "C_C") (pintype "passive"))
      (node (ref "U1") (pin "2") (pinfunction "GND_2") (pintype "bidirectional"))
      (node (ref "U1") (pin "4") (pinfunction "GND_4") (pintype "bidirectional"))
      (node (ref "U2") (pin "2") (pinfunction "GND_2") (pintype "bidirectional"))
      (node (ref "U2") (pin "4") (pinfunction "GND_4") (pintype "bidirectional"))
      (node (ref "U3") (pin "10") (pinfunction "AVSS_RFN_10") (pintype "bidirectional"))
      (node (ref "U3") (pin "11") (pinfunction "TEST_11") (pintype "bidirectional"))
      (node (ref "U3") (pin "20") (pinfunction "DVSS_20") (pintype "bidirectional"))
      (node (ref "U3") (pin "24") (pinfunction "DVSS_24") (pintype "bidirectional"))
      (node (ref "U3") (pin "33") (pinfunction "CLKI_33") (pintype "bidirectional"))
      (node (ref "U3") (pin "35") (pinfunction "DVSS_35") (pintype "bidirectional"))
      (node (ref "U3") (pin "45") (pinfunction "DVSS_45") (pintype "bidirectional"))
      (node (ref "U3") (pin "55") (pinfunction "DVSS_55") (pintype "bidirectional"))
      (node (ref "U3") (pin "58") (pinfunction "AVSS_58") (pintype "bidirectional"))
      (node (ref "U3") (pin "61") (pinfunction "AVSS_61") (pintype "bidirectional"))
      (node (ref "U3") (pin "7") (pinfunction "AVSS_RFP_7") (pintype "bidirectional"))
      (node (ref "U3") (pin "PAD") (pinfunction "PAD_PAD") (pintype "bidirectional"))
      (node (ref "U4") (pin "16") (pinfunction "GND_16") (pintype "bidirectional"))
      (node (ref "U4") (pin "6") (pinfunction "GND_6") (pintype "bidirectional"))
      (node (ref "U6") (pin "3") (pinfunction "GND_3") (pintype "power_in"))
      (node (ref "U7") (pin "2") (pinfunction "VSS_2") (pintype "power_in"))
      (node (ref "USB") (pin "GND") (pinfunction "GND_GND") (pintype "bidirectional"))
      (node (ref "USB") (pin "GND@1") (pinfunction "GND_GND@1") (pintype "bidirectional"))
      (node (ref "USB") (pin "GND@3") (pinfunction "GND_GND@3") (pintype "bidirectional"))
      (node (ref "X1") (pin "2") (pinfunction "2_2") (pintype "passive"))
      (node (ref "X1") (pin "3") (pinfunction "3_3") (pintype "passive"))
    )
    (net (code "29") (name "Net-(ANALOG-Pad1)") (class "Default")
      (node (ref "ANALOG") (pin "1") (pinfunction "1_1") (pintype "passive"))
      (node (ref "R12") (pin "1") (pinfunction "1_1") (pintype "passive"))
    )
    (net (code "30") (name "Net-(ANALOG-Pad5)") (class "Default")
      (node (ref "ANALOG") (pin "5") (pinfunction "5_5") (pintype "passive"))
      (node (ref "R17") (pin "1") (pinfunction "1_1") (pintype "passive"))
    )
    (net (code "31") (name "Net-(ANT2A-1)") (class "Default")
      (node (ref "ANT1") (pin "A") (pinfunction "A_A") (pintype "bidirectional"))
      (node (ref "ANT2") (pin "C") (pinfunction "1_C") (pintype "passive"))
      (node (ref "B1") (pin "1") (pinfunction "OUT_1") (pintype "bidirectional"))
    )
    (net (code "32") (name "Net-(B1-BAL1)") (class "Default")
      (node (ref "B1") (pin "3") (pinfunction "BAL1_3") (pintype "bidirectional"))
      (node (ref "C11") (pin "1") (pinfunction "1_1") (pintype "passive"))
    )
    (net (code "33") (name "Net-(B1-BAL2)") (class "Default")
      (node (ref "B1") (pin "4") (pinfunction "BAL2_4") (pintype "bidirectional"))
      (node (ref "C10") (pin "1") (pinfunction "1_1") (pintype "passive"))
    )
    (net (code "34") (name "Net-(C14-Pad1)") (class "Default")
      (node (ref "C14") (pin "1") (pinfunction "1_1") (pintype "passive"))
      (node (ref "U3") (pin "21") (pinfunction "DVDD_21") (pintype "bidirectional"))
      (node (ref "U3") (pin "22") (pinfunction "DVDD_22") (pintype "bidirectional"))
    )
    (net (code "35") (name "Net-(CHG-PadC)") (class "Default")
      (node (ref "CHG") (pin "C") (pinfunction "C_C") (pintype "passive"))
      (node (ref "R3") (pin "2") (pinfunction "2_2") (pintype "passive"))
    )
    (net (code "36") (name "Net-(D2A-AC)") (class "Default")
      (node (ref "D2") (pin "4") (pinfunction "AC_4") (pintype "passive"))
      (node (ref "R15") (pin "6") (pinfunction "2_6") (pintype "passive"))
      (node (ref "U3") (pin "52") (pinfunction "PE6:T3:INT6_52") (pintype "bidirectional"))
    )
    (net (code "37") (name "Net-(D2B-AC)") (class "Default")
      (node (ref "D2") (pin "1") (pinfunction "AC_1") (pintype "passive"))
      (node (ref "R15") (pin "8") (pinfunction "2_8") (pintype "passive"))
      (node (ref "U3") (pin "51") (pinfunction "PE5:OC3C:INT5_51") (pintype "bidirectional"))
    )
    (net (code "38") (name "Net-(D3A-AC)") (class "Default")
      (node (ref "D3") (pin "4") (pinfunction "AC_4") (pintype "passive"))
      (node (ref "R17") (pin "6") (pinfunction "2_6") (pintype "passive"))
      (node (ref "U3") (pin "26") (pinfunction "PD1:SDA:INT1_26") (pintype "bidirectional"))
    )
    (net (code "39") (name "Net-(D3B-AC)") (class "Default")
      (node (ref "D3") (pin "1") (pinfunction "AC_1") (pintype "passive"))
      (node (ref "R17") (pin "8") (pinfunction "2_8") (pintype "passive"))
      (node (ref "U3") (pin "25") (pinfunction "PD0:SCL:INT0_25") (pintype "bidirectional"))
    )
    (net (code "40") (name "Net-(D4A-AC)") (class "Default")
      (node (ref "D4") (pin "4") (pinfunction "AC_4") (pintype "passive"))
      (node (ref "R15") (pin "4") (pinfunction "2_4") (pintype "passive"))
      (node (ref "U3") (pin "28") (pinfunction "PD3:TXD1:INT3_28") (pintype "bidirectional"))
    )
    (net (code "41") (name "Net-(D4B-AC)") (class "Default")
      (node (ref "D4") (pin "1") (pinfunction "AC_1") (pintype "passive"))
      (node (ref "R15") (pin "2") (pinfunction "2_2") (pintype "passive"))
      (node (ref "U3") (pin "27") (pinfunction "PD2:RXD1:INT2_27") (pintype "bidirectional"))
    )
    (net (code "42") (name "Net-(D5A-AC)") (class "Default")
      (node (ref "D5") (pin "4") (pinfunction "AC_4") (pintype "passive"))
      (node (ref "R14") (pin "2") (pinfunction "2_2") (pintype "passive"))
      (node (ref "U3") (pin "48") (pinfunction "PE2:XCK0:AIN0_48") (pintype "bidirectional"))
    )
    (net (code "43") (name "Net-(D5B-AC)") (class "Default")
      (node (ref "D5") (pin "1") (pinfunction "AC_1") (pintype "passive"))
      (node (ref "R14") (pin "4") (pinfunction "2_4") (pintype "passive"))
      (node (ref "U3") (pin "49") (pinfunction "PE3:OC3A:AIN1_49") (pintype "bidirectional"))
    )
    (net (code "44") (name "Net-(D6A-AC)") (class "Default")
      (node (ref "D6") (pin "4") (pinfunction "AC_4") (pintype "passive"))
      (node (ref "R14") (pin "8") (pinfunction "2_8") (pintype "passive"))
      (node (ref "U3") (pin "53") (pinfunction "PE7:ICP3:INT7:CLK0_53") (pintype "bidirectional"))
    )
    (net (code "45") (name "Net-(D6B-AC)") (class "Default")
      (node (ref "D6") (pin "1") (pinfunction "AC_1") (pintype "passive"))
      (node (ref "R14") (pin "6") (pinfunction "2_6") (pintype "passive"))
      (node (ref "U3") (pin "50") (pinfunction "PE4:OC3B:INT4_50") (pintype "bidirectional"))
    )
    (net (code "46") (name "Net-(D7A-AC)") (class "Default")
      (node (ref "D7") (pin "4") (pinfunction "AC_4") (pintype "passive"))
      (node (ref "R12") (pin "2") (pinfunction "2_2") (pintype "passive"))
      (node (ref "U3") (pin "63") (pinfunction "PF0:ADC0_63") (pintype "bidirectional"))
    )
    (net (code "47") (name "Net-(D7B-AC)") (class "Default")
      (node (ref "D7") (pin "1") (pinfunction "AC_1") (pintype "passive"))
      (node (ref "R12") (pin "4") (pinfunction "2_4") (pintype "passive"))
      (node (ref "U3") (pin "64") (pinfunction "PF1:ADC1_64") (pintype "bidirectional"))
    )
    (net (code "48") (name "Net-(D8A-AC)") (class "Default")
      (node (ref "D8") (pin "4") (pinfunction "AC_4") (pintype "passive"))
      (node (ref "R12") (pin "8") (pinfunction "2_8") (pintype "passive"))
      (node (ref "U3") (pin "2") (pinfunction "PF3:ADC3:DIG4_2") (pintype "bidirectional"))
    )
    (net (code "49") (name "Net-(D8B-AC)") (class "Default")
      (node (ref "D8") (pin "1") (pinfunction "AC_1") (pintype "passive"))
      (node (ref "R12") (pin "6") (pinfunction "2_6") (pintype "passive"))
      (node (ref "U3") (pin "1") (pinfunction "PF2:ADC2:DIG2_1") (pintype "bidirectional"))
    )
    (net (code "50") (name "Net-(D9A-AC)") (class "Default")
      (node (ref "D9") (pin "4") (pinfunction "AC_4") (pintype "passive"))
      (node (ref "R17") (pin "4") (pinfunction "2_4") (pintype "passive"))
      (node (ref "U3") (pin "4") (pinfunction "PF5:ADC5:TMS_4") (pintype "bidirectional"))
    )
    (net (code "51") (name "Net-(D9B-AC)") (class "Default")
      (node (ref "D9") (pin "1") (pinfunction "AC_1") (pintype "passive"))
      (node (ref "R17") (pin "2") (pinfunction "2_2") (pintype "passive"))
      (node (ref "U3") (pin "3") (pinfunction "PF4:ADC4:TCK_3") (pintype "bidirectional"))
    )
    (net (code "52") (name "Net-(D10A-AC)") (class "Default")
      (node (ref "D10") (pin "4") (pinfunction "AC_4") (pintype "passive"))
      (node (ref "R13") (pin "6") (pinfunction "2_6") (pintype "passive"))
      (node (ref "U3") (pin "43") (pinfunction "PB7:OC0A:OC1C:PCINT7_43") (pintype "bidirectional"))
    )
    (net (code "53") (name "Net-(D10B-AC)") (class "Default")
      (node (ref "D10") (pin "1") (pinfunction "AC_1") (pintype "passive"))
      (node (ref "R13") (pin "8") (pinfunction "2_8") (pintype "passive"))
      (node (ref "U3") (pin "42") (pinfunction "PB6:OC1B:PCINT6_42") (pintype "bidirectional"))
    )
    (net (code "54") (name "Net-(D11-J-Pad2)") (class "Default")
      (node (ref "D11-J") (pin "2") (pinfunction "2_2") (pintype "passive"))
      (node (ref "DIGITAL1") (pin "4") (pinfunction "4_4") (pintype "passive"))
    )
    (net (code "55") (name "Net-(D11B-AC)") (class "Default")
      (node (ref "D11") (pin "1") (pinfunction "AC_1") (pintype "passive"))
      (node (ref "R13") (pin "4") (pinfunction "2_4") (pintype "passive"))
      (node (ref "U3") (pin "40") (pinfunction "PB4:OC2A:PCINT4_40") (pintype "bidirectional"))
    )
    (net (code "56") (name "Net-(D12A-AC)") (class "Default")
      (node (ref "D12") (pin "4") (pinfunction "AC_4") (pintype "passive"))
      (node (ref "R16") (pin "4") (pinfunction "2_4") (pintype "passive"))
      (node (ref "U3") (pin "41") (pinfunction "PB5:OC1A:PCINT5_41") (pintype "bidirectional"))
    )
    (net (code "57") (name "Net-(DIGITAL0-Pad1)") (class "Default")
      (node (ref "DIGITAL0") (pin "1") (pinfunction "1_1") (pintype "passive"))
      (node (ref "R15") (pin "1") (pinfunction "1_1") (pintype "passive"))
    )
    (net (code "58") (name "Net-(DIGITAL0-Pad5)") (class "Default")
      (node (ref "DIGITAL0") (pin "5") (pinfunction "5_5") (pintype "passive"))
      (node (ref "R14") (pin "1") (pinfunction "1_1") (pintype "passive"))
    )
    (net (code "59") (name "Net-(DIGITAL1-Pad5)") (class "Default")
      (node (ref "DIGITAL1") (pin "5") (pinfunction "5_5") (pintype "passive"))
      (node (ref "R16") (pin "1") (pinfunction "1_1") (pintype "passive"))
      (node (ref "SPI") (pin "2") (pinfunction "2_2") (pintype "passive"))
    )
    (net (code "60") (name "Net-(L-PadA)") (class "Default")
      (node (ref "L") (pin "A") (pinfunction "A_A") (pintype "passive"))
      (node (ref "R7") (pin "2") (pinfunction "2_2") (pintype "passive"))
    )
    (net (code "61") (name "Net-(PWR-PadA)") (class "Default")
      (node (ref "PWR") (pin "A") (pinfunction "A_A") (pintype "passive"))
      (node (ref "R6") (pin "2") (pinfunction "2_2") (pintype "passive"))
    )
    (net (code "62") (name "Net-(R6-Pad1)") (class "Default")
      (node (ref "R6") (pin "1") (pinfunction "1_1") (pintype "passive"))
      (node (ref "SJ1") (pin "1") (pinfunction "1_1") (pintype "passive"))
    )
    (net (code "63") (name "Net-(R7B-2)") (class "Default")
      (node (ref "R7") (pin "4") (pinfunction "2_4") (pintype "passive"))
      (node (ref "TX") (pin "A") (pinfunction "A_A") (pintype "passive"))
    )
    (net (code "64") (name "Net-(R7D-2)") (class "Default")
      (node (ref "R7") (pin "8") (pinfunction "2_8") (pintype "passive"))
      (node (ref "RX") (pin "A") (pinfunction "A_A") (pintype "passive"))
    )
    (net (code "65") (name "Net-(R8-Pad2)") (class "Default")
      (node (ref "R8") (pin "2") (pinfunction "2_2") (pintype "passive"))
      (node (ref "RFRX") (pin "C") (pinfunction "C_C") (pintype "passive"))
    )
    (net (code "66") (name "Net-(R9-Pad2)") (class "Default")
      (node (ref "R9") (pin "2") (pinfunction "2_2") (pintype "passive"))
      (node (ref "RFTX") (pin "C") (pinfunction "C_C") (pintype "passive"))
    )
    (net (code "67") (name "Net-(R12B-1)") (class "Default")
      (node (ref "ANALOG") (pin "2") (pinfunction "2_2") (pintype "passive"))
      (node (ref "R12") (pin "3") (pinfunction "1_3") (pintype "passive"))
    )
    (net (code "68") (name "Net-(R12C-1)") (class "Default")
      (node (ref "ANALOG") (pin "3") (pinfunction "3_3") (pintype "passive"))
      (node (ref "R12") (pin "5") (pinfunction "1_5") (pintype "passive"))
    )
    (net (code "69") (name "Net-(R12D-1)") (class "Default")
      (node (ref "ANALOG") (pin "4") (pinfunction "4_4") (pintype "passive"))
      (node (ref "R12") (pin "7") (pinfunction "1_7") (pintype "passive"))
    )
    (net (code "70") (name "Net-(R13B-1)") (class "Default")
      (node (ref "DIGITAL1") (pin "1") (pinfunction "1_1") (pintype "passive"))
      (node (ref "R13") (pin "3") (pinfunction "1_3") (pintype "passive"))
    )
    (net (code "71") (name "Net-(R13C-1)") (class "Default")
      (node (ref "DIGITAL1") (pin "2") (pinfunction "2_2") (pintype "passive"))
      (node (ref "R13") (pin "5") (pinfunction "1_5") (pintype "passive"))
    )
    (net (code "72") (name "Net-(R13D-1)") (class "Default")
      (node (ref "DIGITAL1") (pin "3") (pinfunction "3_3") (pintype "passive"))
      (node (ref "R13") (pin "7") (pinfunction "1_7") (pintype "passive"))
    )
    (net (code "73") (name "Net-(R14B-1)") (class "Default")
      (node (ref "DIGITAL0") (pin "6") (pinfunction "6_6") (pintype "passive"))
      (node (ref "R14") (pin "3") (pinfunction "1_3") (pintype "passive"))
    )
    (net (code "74") (name "Net-(R14C-1)") (class "Default")
      (node (ref "DIGITAL0") (pin "7") (pinfunction "7_7") (pintype "passive"))
      (node (ref "R14") (pin "5") (pinfunction "1_5") (pintype "passive"))
    )
    (net (code "75") (name "Net-(R14D-1)") (class "Default")
      (node (ref "DIGITAL0") (pin "8") (pinfunction "8_8") (pintype "passive"))
      (node (ref "R14") (pin "7") (pinfunction "1_7") (pintype "passive"))
    )
    (net (code "76") (name "Net-(R15B-1)") (class "Default")
      (node (ref "DIGITAL0") (pin "2") (pinfunction "2_2") (pintype "passive"))
      (node (ref "R15") (pin "3") (pinfunction "1_3") (pintype "passive"))
    )
    (net (code "77") (name "Net-(R15C-1)") (class "Default")
      (node (ref "DIGITAL0") (pin "3") (pinfunction "3_3") (pintype "passive"))
      (node (ref "R15") (pin "5") (pinfunction "1_5") (pintype "passive"))
    )
    (net (code "78") (name "Net-(R15D-1)") (class "Default")
      (node (ref "DIGITAL0") (pin "4") (pinfunction "4_4") (pintype "passive"))
      (node (ref "R15") (pin "7") (pinfunction "1_7") (pintype "passive"))
    )
    (net (code "79") (name "Net-(R16C-1)") (class "Default")
      (node (ref "DIGITAL1") (pin "6") (pinfunction "6_6") (pintype "passive"))
      (node (ref "R16") (pin "5") (pinfunction "1_5") (pintype "passive"))
      (node (ref "SPI") (pin "1") (pinfunction "1_1") (pintype "passive"))
    )
    (net (code "80") (name "Net-(R16D-1)") (class "Default")
      (node (ref "D11-J") (pin "1") (pinfunction "1_1") (pintype "passive"))
      (node (ref "R16") (pin "7") (pinfunction "1_7") (pintype "passive"))
      (node (ref "SPI") (pin "3") (pinfunction "3_3") (pintype "passive"))
    )
    (net (code "81") (name "Net-(R17B-1)") (class "Default")
      (node (ref "ANALOG") (pin "6") (pinfunction "6_6") (pintype "passive"))
      (node (ref "R17") (pin "3") (pinfunction "1_3") (pintype "passive"))
    )
    (net (code "82") (name "Net-(U3-AVDD)") (class "Default")
      (node (ref "C16") (pin "2") (pinfunction "2_2") (pintype "passive"))
      (node (ref "U3") (pin "60") (pinfunction "AVDD_60") (pintype "bidirectional"))
    )
    (net (code "83") (name "Net-(U3-PF7:ADC7:TDI)") (class "Default")
      (node (ref "AUX") (pin "11") (pinfunction "11_11") (pintype "passive"))
      (node (ref "U3") (pin "6") (pinfunction "PF7:ADC7:TDI_6") (pintype "bidirectional"))
    )
    (net (code "84") (name "Net-(U3-PG0:DIG3)") (class "Default")
      (node (ref "AUX") (pin "12") (pinfunction "12_12") (pintype "passive"))
      (node (ref "U3") (pin "14") (pinfunction "PG0:DIG3_14") (pintype "bidirectional"))
    )
    (net (code "85") (name "Net-(U3-PG1:DIG1)") (class "Default")
      (node (ref "AUX") (pin "9") (pinfunction "9_9") (pintype "passive"))
      (node (ref "U3") (pin "15") (pinfunction "PG1:DIG1_15") (pintype "bidirectional"))
    )
    (net (code "86") (name "Net-(U3-PG2:AMR)") (class "Default")
      (node (ref "AUX") (pin "10") (pinfunction "10_10") (pintype "passive"))
      (node (ref "U3") (pin "16") (pinfunction "PG2:AMR_16") (pintype "bidirectional"))
    )
    (net (code "87") (name "Net-(U3-PG3:TOSC2)") (class "Default")
      (node (ref "AUX") (pin "7") (pinfunction "7_7") (pintype "passive"))
      (node (ref "C8") (pin "2") (pinfunction "2_2") (pintype "passive"))
      (node (ref "Q2") (pin "1") (pinfunction "1_1") (pintype "passive"))
      (node (ref "U3") (pin "17") (pinfunction "PG3:TOSC2_17") (pintype "bidirectional"))
    )
    (net (code "88") (name "Net-(U3-PG4:TOSC1)") (class "Default")
      (node (ref "AUX") (pin "8") (pinfunction "8_8") (pintype "passive"))
      (node (ref "C7") (pin "2") (pinfunction "2_2") (pintype "passive"))
      (node (ref "Q2") (pin "2") (pinfunction "2_2") (pintype "passive"))
      (node (ref "U3") (pin "18") (pinfunction "PG4:TOSC1_18") (pintype "bidirectional"))
    )
    (net (code "89") (name "Net-(U3-PG5:OC0B)") (class "Default")
      (node (ref "AUX") (pin "5") (pinfunction "5_5") (pintype "passive"))
      (node (ref "U3") (pin "19") (pinfunction "PG5:OC0B_19") (pintype "bidirectional"))
    )
    (net (code "90") (name "Net-(U3-RFN)") (class "Default")
      (node (ref "C11") (pin "2") (pinfunction "2_2") (pintype "passive"))
      (node (ref "U3") (pin "9") (pinfunction "RFN_9") (pintype "bidirectional"))
    )
    (net (code "91") (name "Net-(U3-RFP)") (class "Default")
      (node (ref "C10") (pin "2") (pinfunction "2_2") (pintype "passive"))
      (node (ref "U3") (pin "8") (pinfunction "RFP_8") (pintype "bidirectional"))
    )
    (net (code "92") (name "Net-(U3-XTAL1)") (class "Default")
      (node (ref "C2") (pin "2") (pinfunction "2_2") (pintype "passive"))
      (node (ref "Q1") (pin "2") (pinfunction "2_2") (pintype "passive"))
      (node (ref "U3") (pin "56") (pinfunction "XTAL1_56") (pintype "bidirectional"))
    )
    (net (code "93") (name "Net-(U3-XTAL2)") (class "Default")
      (node (ref "C1") (pin "2") (pinfunction "2_2") (pintype "passive"))
      (node (ref "Q1") (pin "1") (pinfunction "1_1") (pintype "passive"))
      (node (ref "U3") (pin "57") (pinfunction "XTAL2_57") (pintype "bidirectional"))
    )
    (net (code "94") (name "Net-(U4-3V3OUT)") (class "Default")
      (node (ref "C17") (pin "1") (pinfunction "1_1") (pintype "passive"))
      (node (ref "U4") (pin "13") (pinfunction "3V3OUT_13") (pintype "bidirectional"))
      (node (ref "U4") (pin "14") (pinfunction "RESET#_14") (pintype "bidirectional"))
      (node (ref "U4") (pin "3") (pinfunction "VCCIO_3") (pintype "bidirectional"))
    )
    (net (code "95") (name "Net-(U4-DTR#)") (class "Default")
      (node (ref "C9") (pin "1") (pinfunction "1_1") (pintype "passive"))
      (node (ref "U4") (pin "1") (pinfunction "DTR#_1") (pintype "bidirectional"))
    )
    (net (code "96") (name "Net-(U4-USBDM)") (class "Default")
      (node (ref "R4") (pin "2") (pinfunction "2_2") (pintype "passive"))
      (node (ref "U4") (pin "12") (pinfunction "USBDM_12") (pintype "bidirectional"))
    )
    (net (code "97") (name "Net-(U4-USBDP)") (class "Default")
      (node (ref "R5") (pin "2") (pinfunction "2_2") (pintype "passive"))
      (node (ref "U4") (pin "11") (pinfunction "USBDP_11") (pintype "bidirectional"))
    )
    (net (code "98") (name "Net-(U4-VCC)") (class "Default")
      (node (ref "L1") (pin "2") (pinfunction "2_2") (pintype "passive"))
      (node (ref "U4") (pin "15") (pinfunction "VCC_15") (pintype "bidirectional"))
    )
    (net (code "99") (name "Net-(U7-PROG)") (class "Default")
      (node (ref "R2") (pin "2") (pinfunction "2_2") (pintype "passive"))
      (node (ref "U7") (pin "5") (pinfunction "PROG_5") (pintype "input"))
    )
    (net (code "100") (name "Net-(U7-STAT)") (class "Default")
      (node (ref "R3") (pin "1") (pinfunction "1_1") (pintype "passive"))
      (node (ref "U7") (pin "1") (pinfunction "STAT_1") (pintype "output"))
    )
    (net (code "101") (name "Net-(U7-VBAT)") (class "Default")
      (node (ref "BAT-TEST") (pin "TP") (pinfunction "TP_TP") (pintype "input"))
      (node (ref "C3") (pin "1") (pinfunction "1_1") (pintype "passive"))
      (node (ref "CHG") (pin "A") (pinfunction "A_A") (pintype "passive"))
      (node (ref "D14") (pin "A") (pinfunction "A_A") (pintype "passive"))
      (node (ref "JP1") (pin "2") (pinfunction "2_2") (pintype "passive"))
      (node (ref "R10") (pin "1") (pinfunction "1_1") (pintype "passive"))
      (node (ref "U7") (pin "3") (pinfunction "VBAT_3") (pintype "power_in"))
    )
    (net (code "102") (name "unconnected-(POWER-Pad1)") (class "Default")
      (node (ref "POWER") (pin "1") (pinfunction "1_1") (pintype "passive"))
    )
    (net (code "103") (name "unconnected-(U3-~{RESET_OUT}-Pad13)") (class "Default")
      (node (ref "U3") (pin "13") (pinfunction "~{RESET_OUT}_13") (pintype "bidirectional"))
    )
    (net (code "104") (name "unconnected-(U4-CBUS0-Pad18)") (class "Default")
      (node (ref "U4") (pin "18") (pinfunction "CBUS0_18") (pintype "bidirectional"))
    )
    (net (code "105") (name "unconnected-(U4-CBUS3-Pad19)") (class "Default")
      (node (ref "U4") (pin "19") (pinfunction "CBUS3_19") (pintype "bidirectional"))
    )
    (net (code "106") (name "unconnected-(U4-CTS#-Pad9)") (class "Default")
      (node (ref "U4") (pin "9") (pinfunction "CTS#_9") (pintype "bidirectional"))
    )
    (net (code "107") (name "unconnected-(U4-DCD#-Pad8)") (class "Default")
      (node (ref "U4") (pin "8") (pinfunction "DCD#_8") (pintype "bidirectional"))
    )
    (net (code "108") (name "unconnected-(U4-DSR#-Pad7)") (class "Default")
      (node (ref "U4") (pin "7") (pinfunction "DSR#_7") (pintype "bidirectional"))
    )
    (net (code "109") (name "unconnected-(U4-RI#-Pad5)") (class "Default")
      (node (ref "U4") (pin "5") (pinfunction "RI#_5") (pintype "bidirectional"))
    )
    (net (code "110") (name "unconnected-(U4-RTS#-Pad2)") (class "Default")
      (node (ref "U4") (pin "2") (pinfunction "RTS#_2") (pintype "bidirectional"))
    )
  )
)
